# Receiver.net
KiCad netlist of a schematic drawn in Altium Designer
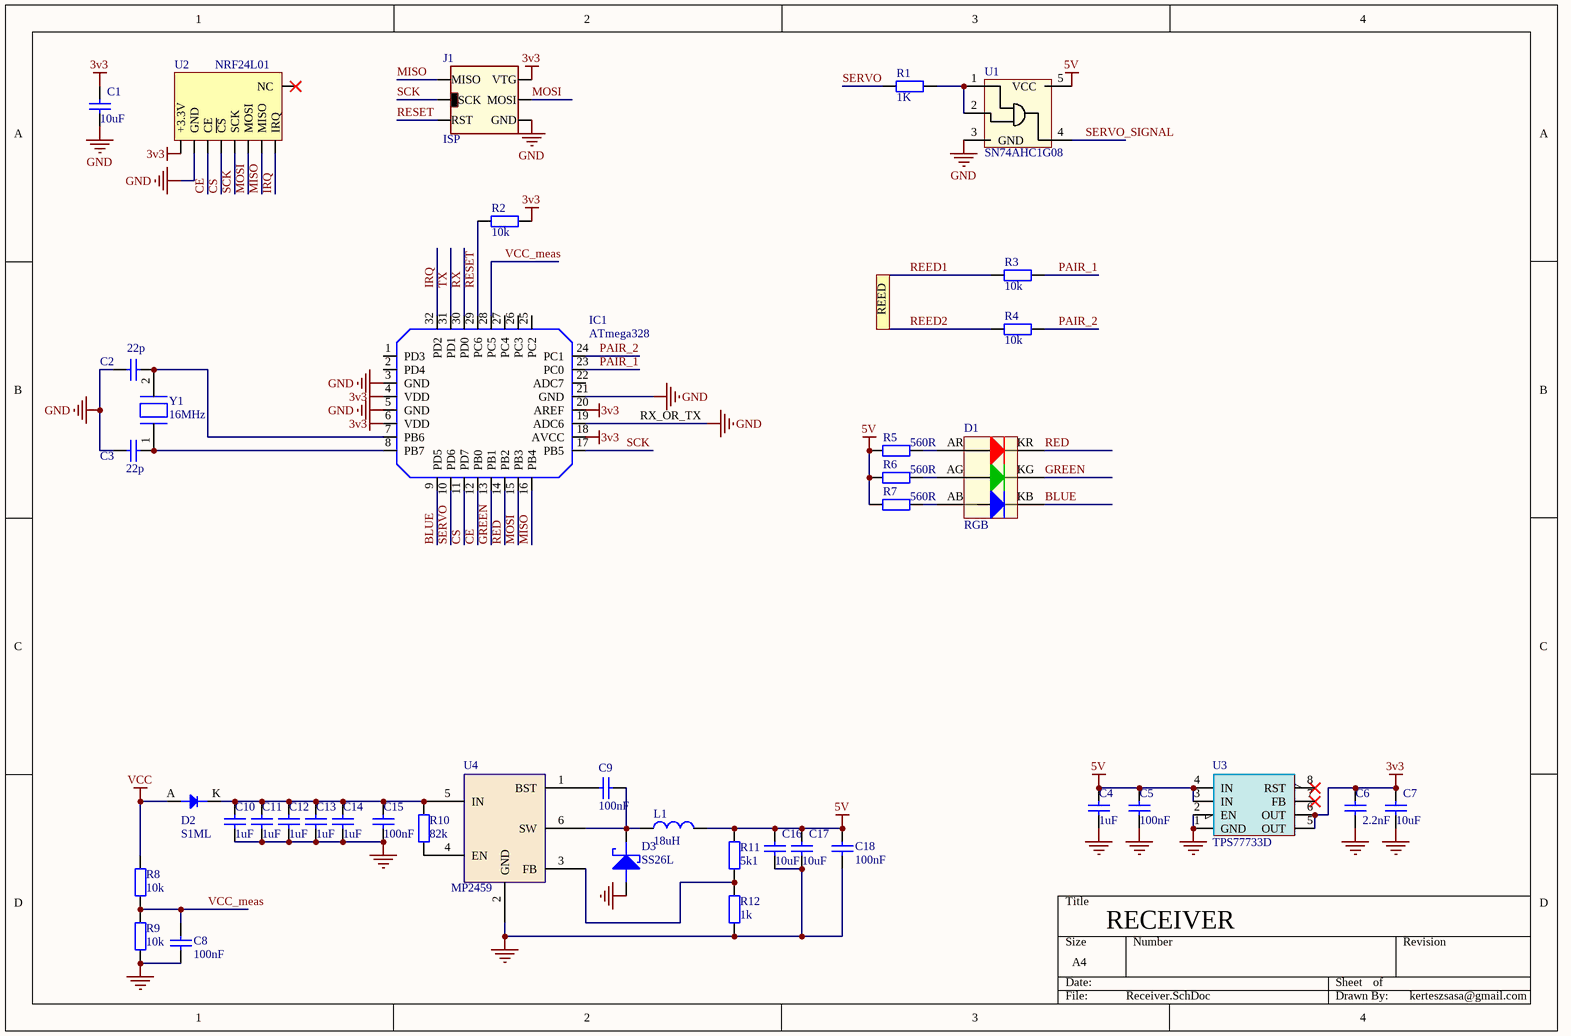
[diagram p0: Receiver.SchDoc]

(export (version "E")
  (design (tool "Eeschema 10.0.6"))
  (components
    (comp (ref "C1")
      (value "10uF")
      (footprint "FP_0603_CAP_080")
      (description "Capacitor")
      (libsource (lib "Miscellaneous Devices") (part "Cap"))
    )
    (comp (ref "C2")
      (value "22p")
      (footprint "FP_0603_CAP_080")
      (description "Capacitor")
      (libsource (lib "Miscellaneous Devices") (part "Cap"))
    )
    (comp (ref "C3")
      (value "22p")
      (footprint "FP_0603_CAP_080")
      (description "Capacitor")
      (libsource (lib "Miscellaneous Devices") (part "Cap"))
    )
    (comp (ref "C4")
      (value "1uF")
      (footprint "FP_0603_CAP_080")
      (description "Capacitor")
      (libsource (lib "Miscellaneous Devices") (part "Cap"))
    )
    (comp (ref "C5")
      (value "100nF")
      (footprint "FP_0603_CAP_080")
      (description "Capacitor")
      (libsource (lib "Miscellaneous Devices") (part "Cap"))
    )
    (comp (ref "C6")
      (value "2.2nF")
      (footprint "FP_0603_CAP_080")
      (description "Capacitor")
      (libsource (lib "Miscellaneous Devices") (part "Cap"))
    )
    (comp (ref "C7")
      (value "10uF")
      (footprint "FP_0603_CAP_080")
      (description "Capacitor")
      (libsource (lib "Miscellaneous Devices") (part "Cap"))
    )
    (comp (ref "C8")
      (value "100nF")
      (footprint "FP_0603_CAP_080")
      (description "Capacitor")
      (libsource (lib "Miscellaneous Devices") (part "Cap"))
    )
    (comp (ref "C9")
      (value "100nF")
      (footprint "FP_0603_CAP_080")
      (description "Capacitor")
      (libsource (lib "Miscellaneous Devices") (part "Cap"))
    )
    (comp (ref "C10")
      (value "1uF")
      (footprint "FP_0805_CAP_145")
      (description "Capacitor")
      (libsource (lib "Capacitor") (part "CAP"))
    )
    (comp (ref "C11")
      (value "1uF")
      (footprint "FP_0805_CAP_145")
      (description "Capacitor")
      (libsource (lib "Capacitor") (part "CAP"))
    )
    (comp (ref "C12")
      (value "1uF")
      (footprint "FP_0805_CAP_145")
      (description "Capacitor")
      (libsource (lib "Capacitor") (part "CAP"))
    )
    (comp (ref "C13")
      (value "1uF")
      (footprint "FP_0805_CAP_145")
      (description "Capacitor")
      (libsource (lib "Capacitor") (part "CAP"))
    )
    (comp (ref "C14")
      (value "1uF")
      (footprint "FP_0805_CAP_145")
      (description "Capacitor")
      (libsource (lib "Capacitor") (part "CAP"))
    )
    (comp (ref "C15")
      (value "100nF")
      (footprint "FP_0603_CAP_080")
      (description "Capacitor")
      (libsource (lib "Miscellaneous Devices") (part "Cap"))
    )
    (comp (ref "C16")
      (value "10uF")
      (footprint "FP_0603_CAP_080")
      (description "Capacitor")
      (libsource (lib "Miscellaneous Devices") (part "Cap"))
    )
    (comp (ref "C17")
      (value "10uF")
      (footprint "FP_0603_CAP_080")
      (description "Capacitor")
      (libsource (lib "Miscellaneous Devices") (part "Cap"))
    )
    (comp (ref "C18")
      (value "100nF")
      (footprint "FP_0603_CAP_080")
      (description "Capacitor")
      (libsource (lib "Miscellaneous Devices") (part "Cap"))
    )
    (comp (ref "D1")
      (value "RGB")
      (footprint "RGB_LED_5.0x5.0mm")
      (description "LED_RGB_6_PIN")
      (libsource (lib "Led_optical") (part "LED_RGB_6_PIN"))
    )
    (comp (ref "D2")
      (value "S1ML")
      (footprint "subsma")
      (description "Diode")
      (libsource (lib "Diode") (part "DIODE"))
    )
    (comp (ref "D3")
      (value "SS26L")
      (footprint "subsma")
      (description "NXP - PMEG3020EJ,115 - SCHOTTKY RECT 30V 2A SOD323F")
      (libsource (lib "Diode") (part "SCHOTTKY"))
    )
    (comp (ref "IC1") (value "ATmega328") (footprint "TQFP32_N") (libsource (lib "uC") (part "ATmega328")))
    (comp (ref "J1")
      (value "ISP")
      (footprint "AVR_ISP")
      (description "Programozó csatlakozó")
      (libsource (lib "Connector") (part "ISP"))
    )
    (comp (ref "L1")
      (value "18uH")
      (footprint "SDR0403_IND_4.5x5mm")
      (description "Inductor")
      (libsource (lib "Inductor") (part "L"))
    )
    (comp (ref "R1")
      (value "1K")
      (footprint "FP_0603_RES")
      (description "Resistor")
      (libsource (lib "") (part "RES_1"))
    )
    (comp (ref "R2")
      (value "10k")
      (footprint "FP_0603_RES")
      (description "Resistor")
      (libsource (lib "Miscellaneous Devices") (part "Res3"))
    )
    (comp (ref "R3")
      (value "10k")
      (footprint "FP_0603_RES")
      (description "Resistor")
      (libsource (lib "Miscellaneous Devices") (part "Res3"))
    )
    (comp (ref "R4")
      (value "10k")
      (footprint "FP_0603_RES")
      (description "Resistor")
      (libsource (lib "Miscellaneous Devices") (part "Res3"))
    )
    (comp (ref "R5")
      (value "560R")
      (footprint "FP_0603_RES")
      (description "Resistor")
      (libsource (lib "") (part "Res3_1"))
    )
    (comp (ref "R6")
      (value "560R")
      (footprint "FP_0603_RES")
      (description "Resistor")
      (libsource (lib "") (part "Res3_1"))
    )
    (comp (ref "R7")
      (value "560R")
      (footprint "FP_0603_RES")
      (description "Resistor")
      (libsource (lib "") (part "Res3_1"))
    )
    (comp (ref "R8")
      (value "10k")
      (footprint "FP_0603_RES")
      (description "Resistor")
      (libsource (lib "") (part "Res3_3"))
    )
    (comp (ref "R9")
      (value "10k")
      (footprint "FP_0603_RES")
      (description "Resistor")
      (libsource (lib "") (part "Res3_3"))
    )
    (comp (ref "R10")
      (value "82k")
      (footprint "FP_0603_RES")
      (description "Resistor")
      (libsource (lib "Resistor") (part "RES"))
    )
    (comp (ref "R11")
      (value "5k1")
      (footprint "FP_0603_RES")
      (description "Resistor")
      (libsource (lib "") (part "Res3_2"))
    )
    (comp (ref "R12")
      (value "1k")
      (footprint "FP_0603_RES")
      (description "Resistor")
      (libsource (lib "") (part "Res3_2"))
    )
    (comp (ref "U1")
      (value "SN74AHC1G08")
      (footprint "GATE_SOT23-5")
      (description "1x2-INPUT AND-GATE")
      (libsource (lib "Logic_gate") (part "SN74AHC1G08"))
    )
    (comp (ref "U2")
      (value "NRF24L01")
      (footprint "NRF24L01_SMD")
      (description "2.4Ghz RF module")
      (libsource (lib "Modul") (part "NRF24L01"))
    )
    (comp (ref "U3")
      (value "TPS77733D")
      (footprint "DIGITAL_SOIC8")
      (description "LDO Voltage Regulators Fast-Tran-Res 750-mA")
      (libsource (lib "TPS77733D") (part "TPS77733D"))
    )
    (comp (ref "U4")
      (value "MP2459")
      (footprint "Supply_SOT23-6")
      (description "0.5A, 55V, 480kHz  Step-Down Converter in a TSOT23-6")
      (libsource (lib "Supply") (part "MP2459"))
    )
    (comp (ref "Y1")
      (value "16MHz")
      (footprint "FP_CRYSTAL_HC49_SMD")
      (description "Standard HC49 quartz")
      (libsource (lib "Fufi_altium_lib") (part "XTAL HC49"))
    )
  )
  (nets
    (net (code "1") (name "/BLUE") (class "Default")
      (node (ref "D1") (pin "KB") (pinfunction "R_KB") (pintype "passive"))
      (node (ref "IC1") (pin "9") (pinfunction "PD5_9") (pintype "passive"))
    )
    (net (code "2") (name "/CE") (class "Default")
      (node (ref "IC1") (pin "12") (pinfunction "PB0_12") (pintype "passive"))
      (node (ref "U2") (pin "3") (pinfunction "CE_3") (pintype "passive"))
    )
    (net (code "3") (name "/CS") (class "Default")
      (node (ref "IC1") (pin "11") (pinfunction "PD7_11") (pintype "passive"))
      (node (ref "U2") (pin "4") (pinfunction "~{CS}_4") (pintype "passive"))
    )
    (net (code "4") (name "/GREEN") (class "Default")
      (node (ref "D1") (pin "KG") (pinfunction "G_KG") (pintype "passive"))
      (node (ref "IC1") (pin "13") (pinfunction "PB1_13") (pintype "passive"))
    )
    (net (code "5") (name "/IRQ") (class "Default")
      (node (ref "IC1") (pin "32") (pinfunction "PD2_32") (pintype "passive"))
      (node (ref "U2") (pin "8") (pinfunction "IRQ_8") (pintype "passive"))
    )
    (net (code "6") (name "/MISO") (class "Default")
      (node (ref "IC1") (pin "16") (pinfunction "PB4_16") (pintype "passive"))
      (node (ref "J1") (pin "1") (pinfunction "MISO_1") (pintype "passive"))
      (node (ref "U2") (pin "7") (pinfunction "MISO_7") (pintype "passive"))
    )
    (net (code "7") (name "/MOSI") (class "Default")
      (node (ref "IC1") (pin "15") (pinfunction "PB3_15") (pintype "passive"))
      (node (ref "J1") (pin "4") (pinfunction "MOSI_4") (pintype "passive"))
      (node (ref "U2") (pin "6") (pinfunction "MOSI_6") (pintype "passive"))
    )
    (net (code "8") (name "/PAIR_1") (class "Default")
      (node (ref "IC1") (pin "23") (pinfunction "PC0_23") (pintype "passive"))
      (node (ref "R3") (pin "2") (pinfunction "2_2") (pintype "passive"))
    )
    (net (code "9") (name "/PAIR_2") (class "Default")
      (node (ref "IC1") (pin "24") (pinfunction "PC1_24") (pintype "passive"))
      (node (ref "R4") (pin "2") (pinfunction "2_2") (pintype "passive"))
    )
    (net (code "10") (name "/RED") (class "Default")
      (node (ref "D1") (pin "KR") (pinfunction "B_KR") (pintype "passive"))
      (node (ref "IC1") (pin "14") (pinfunction "PB2_14") (pintype "passive"))
    )
    (net (code "11") (name "/REED1") (class "Default")
      (node (ref "R3") (pin "1") (pinfunction "1_1") (pintype "passive"))
    )
    (net (code "12") (name "/REED2") (class "Default")
      (node (ref "R4") (pin "1") (pinfunction "1_1") (pintype "passive"))
    )
    (net (code "13") (name "/RESET") (class "Default")
      (node (ref "IC1") (pin "29") (pinfunction "PC6_29") (pintype "passive"))
      (node (ref "J1") (pin "5") (pinfunction "RST_5") (pintype "passive"))
      (node (ref "R2") (pin "1") (pinfunction "1_1") (pintype "passive"))
    )
    (net (code "14") (name "/RX") (class "Default")
      (node (ref "IC1") (pin "30") (pinfunction "PD0_30") (pintype "passive"))
    )
    (net (code "15") (name "/SCK") (class "Default")
      (node (ref "IC1") (pin "17") (pinfunction "PB5_17") (pintype "passive"))
      (node (ref "J1") (pin "3") (pinfunction "SCK_3") (pintype "passive"))
      (node (ref "U2") (pin "5") (pinfunction "SCK_5") (pintype "passive"))
    )
    (net (code "16") (name "/SERVO") (class "Default")
      (node (ref "IC1") (pin "10") (pinfunction "PD6_10") (pintype "passive"))
      (node (ref "R1") (pin "1") (pinfunction "1_1") (pintype "passive"))
    )
    (net (code "17") (name "/SERVO_SIGNAL") (class "Default")
      (node (ref "U1") (pin "4") (pinfunction "Y_4") (pintype "passive"))
    )
    (net (code "18") (name "/TX") (class "Default")
      (node (ref "IC1") (pin "31") (pinfunction "PD1_31") (pintype "passive"))
    )
    (net (code "19") (name "/VCC_meas") (class "Default")
      (node (ref "C8") (pin "1") (pinfunction "1_1") (pintype "passive"))
      (node (ref "IC1") (pin "28") (pinfunction "PC5_28") (pintype "passive"))
      (node (ref "R8") (pin "1") (pinfunction "1_1") (pintype "passive"))
      (node (ref "R9") (pin "2") (pinfunction "2_2") (pintype "passive"))
    )
    (net (code "20") (name "3v3") (class "Default")
      (node (ref "C1") (pin "2") (pinfunction "2_2") (pintype "passive"))
      (node (ref "C6") (pin "2") (pinfunction "2_2") (pintype "passive"))
      (node (ref "C7") (pin "2") (pinfunction "2_2") (pintype "passive"))
      (node (ref "IC1") (pin "18") (pinfunction "AVCC_18") (pintype "passive"))
      (node (ref "IC1") (pin "20") (pinfunction "AREF_20") (pintype "passive"))
      (node (ref "IC1") (pin "4") (pinfunction "VDD_4") (pintype "passive"))
      (node (ref "IC1") (pin "6") (pinfunction "VDD_6") (pintype "passive"))
      (node (ref "J1") (pin "2") (pinfunction "VTG_2") (pintype "passive"))
      (node (ref "R2") (pin "2") (pinfunction "2_2") (pintype "passive"))
      (node (ref "U2") (pin "1") (pinfunction "+3.3V_1") (pintype "passive"))
      (node (ref "U3") (pin "5") (pinfunction "OUT_5") (pintype "passive"))
      (node (ref "U3") (pin "6") (pinfunction "OUT_6") (pintype "passive"))
    )
    (net (code "21") (name "5V") (class "Default")
      (node (ref "C16") (pin "2") (pinfunction "2_2") (pintype "passive"))
      (node (ref "C17") (pin "2") (pinfunction "2_2") (pintype "passive"))
      (node (ref "C18") (pin "1") (pinfunction "1_1") (pintype "passive"))
      (node (ref "C4") (pin "2") (pinfunction "2_2") (pintype "passive"))
      (node (ref "C5") (pin "2") (pinfunction "2_2") (pintype "passive"))
      (node (ref "L1") (pin "2") (pinfunction "2_2") (pintype "passive"))
      (node (ref "R11") (pin "1") (pinfunction "1_1") (pintype "passive"))
      (node (ref "R5") (pin "2") (pinfunction "2_2") (pintype "passive"))
      (node (ref "R6") (pin "2") (pinfunction "2_2") (pintype "passive"))
      (node (ref "R7") (pin "2") (pinfunction "2_2") (pintype "passive"))
      (node (ref "U1") (pin "5") (pinfunction "VCC_5") (pintype "passive"))
      (node (ref "U3") (pin "3") (pinfunction "IN_3") (pintype "passive"))
      (node (ref "U3") (pin "4") (pinfunction "IN_4") (pintype "passive"))
    )
    (net (code "22") (name "GND") (class "Default")
      (node (ref "C1") (pin "1") (pinfunction "1_1") (pintype "passive"))
      (node (ref "C10") (pin "1") (pinfunction "1_1") (pintype "passive"))
      (node (ref "C11") (pin "1") (pinfunction "1_1") (pintype "passive"))
      (node (ref "C12") (pin "1") (pinfunction "1_1") (pintype "passive"))
      (node (ref "C13") (pin "1") (pinfunction "1_1") (pintype "passive"))
      (node (ref "C14") (pin "1") (pinfunction "1_1") (pintype "passive"))
      (node (ref "C15") (pin "2") (pinfunction "2_2") (pintype "passive"))
      (node (ref "C16") (pin "1") (pinfunction "1_1") (pintype "passive"))
      (node (ref "C17") (pin "1") (pinfunction "1_1") (pintype "passive"))
      (node (ref "C18") (pin "2") (pinfunction "2_2") (pintype "passive"))
      (node (ref "C2") (pin "1") (pinfunction "1_1") (pintype "passive"))
      (node (ref "C3") (pin "1") (pinfunction "1_1") (pintype "passive"))
      (node (ref "C4") (pin "1") (pinfunction "1_1") (pintype "passive"))
      (node (ref "C5") (pin "1") (pinfunction "1_1") (pintype "passive"))
      (node (ref "C6") (pin "1") (pinfunction "1_1") (pintype "passive"))
      (node (ref "C7") (pin "1") (pinfunction "1_1") (pintype "passive"))
      (node (ref "C8") (pin "2") (pinfunction "2_2") (pintype "passive"))
      (node (ref "D3") (pin "A") (pinfunction "A_A") (pintype "passive"))
      (node (ref "IC1") (pin "19") (pinfunction "ADC6_19") (pintype "passive"))
      (node (ref "IC1") (pin "21") (pinfunction "GND_21") (pintype "passive"))
      (node (ref "IC1") (pin "3") (pinfunction "GND_3") (pintype "passive"))
      (node (ref "IC1") (pin "5") (pinfunction "GND_5") (pintype "passive"))
      (node (ref "J1") (pin "6") (pinfunction "GND_6") (pintype "passive"))
      (node (ref "R12") (pin "2") (pinfunction "2_2") (pintype "passive"))
      (node (ref "R9") (pin "1") (pinfunction "1_1") (pintype "passive"))
      (node (ref "U1") (pin "3") (pinfunction "GND_3") (pintype "passive"))
      (node (ref "U2") (pin "2") (pinfunction "GND_2") (pintype "passive"))
      (node (ref "U3") (pin "1") (pinfunction "GND_1") (pintype "passive"))
      (node (ref "U3") (pin "2") (pinfunction "EN_2") (pintype "passive"))
      (node (ref "U4") (pin "2") (pinfunction "GND_2") (pintype "passive"))
    )
    (net (code "23") (name "Net-(D1-A-PadAB)") (class "Default")
      (node (ref "D1") (pin "AB") (pinfunction "A_AB") (pintype "passive"))
      (node (ref "R7") (pin "1") (pinfunction "1_1") (pintype "passive"))
    )
    (net (code "24") (name "Net-(D1-A-PadAG)") (class "Default")
      (node (ref "D1") (pin "AG") (pinfunction "A_AG") (pintype "passive"))
      (node (ref "R6") (pin "1") (pinfunction "1_1") (pintype "passive"))
    )
    (net (code "25") (name "Net-(D1-A-PadAR)") (class "Default")
      (node (ref "D1") (pin "AR") (pinfunction "A_AR") (pintype "passive"))
      (node (ref "R5") (pin "1") (pinfunction "1_1") (pintype "passive"))
    )
    (net (code "26") (name "Net-(IC1-PB6)") (class "Default")
      (node (ref "C2") (pin "2") (pinfunction "2_2") (pintype "passive"))
      (node (ref "IC1") (pin "7") (pinfunction "PB6_7") (pintype "passive"))
      (node (ref "Y1") (pin "2") (pinfunction "2_2") (pintype "passive"))
    )
    (net (code "27") (name "Net-(IC1-PB7)") (class "Default")
      (node (ref "C3") (pin "2") (pinfunction "2_2") (pintype "passive"))
      (node (ref "IC1") (pin "8") (pinfunction "PB7_8") (pintype "passive"))
      (node (ref "Y1") (pin "1") (pinfunction "1_1") (pintype "passive"))
    )
    (net (code "28") (name "Net-(U1-A)") (class "Default")
      (node (ref "R1") (pin "2") (pinfunction "2_2") (pintype "passive"))
      (node (ref "U1") (pin "1") (pinfunction "A_1") (pintype "passive"))
      (node (ref "U1") (pin "2") (pinfunction "B_2") (pintype "passive"))
    )
    (net (code "29") (name "Net-(U4-BST)") (class "Default")
      (node (ref "C9") (pin "2") (pinfunction "2_2") (pintype "passive"))
      (node (ref "U4") (pin "1") (pinfunction "BST_1") (pintype "passive"))
    )
    (net (code "30") (name "Net-(U4-EN)") (class "Default")
      (node (ref "R10") (pin "2") (pinfunction "2_2") (pintype "passive"))
      (node (ref "U4") (pin "4") (pinfunction "EN_4") (pintype "passive"))
    )
    (net (code "31") (name "Net-(U4-FB)") (class "Default")
      (node (ref "R11") (pin "2") (pinfunction "2_2") (pintype "passive"))
      (node (ref "R12") (pin "1") (pinfunction "1_1") (pintype "passive"))
      (node (ref "U4") (pin "3") (pinfunction "FB_3") (pintype "passive"))
    )
    (net (code "32") (name "Net-(U4-IN)") (class "Default")
      (node (ref "C10") (pin "2") (pinfunction "2_2") (pintype "passive"))
      (node (ref "C11") (pin "2") (pinfunction "2_2") (pintype "passive"))
      (node (ref "C12") (pin "2") (pinfunction "2_2") (pintype "passive"))
      (node (ref "C13") (pin "2") (pinfunction "2_2") (pintype "passive"))
      (node (ref "C14") (pin "2") (pinfunction "2_2") (pintype "passive"))
      (node (ref "C15") (pin "1") (pinfunction "1_1") (pintype "passive"))
      (node (ref "D2") (pin "K") (pinfunction "K_K") (pintype "passive"))
      (node (ref "R10") (pin "1") (pinfunction "1_1") (pintype "passive"))
      (node (ref "U4") (pin "5") (pinfunction "IN_5") (pintype "passive"))
    )
    (net (code "33") (name "Net-(U4-SW)") (class "Default")
      (node (ref "C9") (pin "1") (pinfunction "1_1") (pintype "passive"))
      (node (ref "D3") (pin "K") (pinfunction "K_K") (pintype "passive"))
      (node (ref "L1") (pin "1") (pinfunction "1_1") (pintype "passive"))
      (node (ref "U4") (pin "6") (pinfunction "SW_6") (pintype "passive"))
    )
    (net (code "34") (name "VCC") (class "Default")
      (node (ref "D2") (pin "A") (pinfunction "A_A") (pintype "passive"))
      (node (ref "R8") (pin "2") (pinfunction "2_2") (pintype "passive"))
    )
    (net (code "35") (name "unconnected-(IC1-ADC7-Pad22)") (class "Default")
      (node (ref "IC1") (pin "22") (pinfunction "ADC7_22") (pintype "passive"))
    )
    (net (code "36") (name "unconnected-(IC1-PC2-Pad25)") (class "Default")
      (node (ref "IC1") (pin "25") (pinfunction "PC2_25") (pintype "passive"))
    )
    (net (code "37") (name "unconnected-(IC1-PC3-Pad26)") (class "Default")
      (node (ref "IC1") (pin "26") (pinfunction "PC3_26") (pintype "passive"))
    )
    (net (code "38") (name "unconnected-(IC1-PC4-Pad27)") (class "Default")
      (node (ref "IC1") (pin "27") (pinfunction "PC4_27") (pintype "passive"))
    )
    (net (code "39") (name "unconnected-(IC1-PD3-Pad1)") (class "Default")
      (node (ref "IC1") (pin "1") (pinfunction "PD3_1") (pintype "passive"))
    )
    (net (code "40") (name "unconnected-(IC1-PD4-Pad2)") (class "Default")
      (node (ref "IC1") (pin "2") (pinfunction "PD4_2") (pintype "passive"))
    )
    (net (code "41") (name "unconnected-(U2-NC-Pad9)") (class "Default")
      (node (ref "U2") (pin "9") (pinfunction "NC_9") (pintype "passive+no_connect"))
    )
    (net (code "42") (name "unconnected-(U3-FB-Pad7)") (class "Default")
      (node (ref "U3") (pin "7") (pinfunction "FB_7") (pintype "passive+no_connect"))
    )
    (net (code "43") (name "unconnected-(U3-RST-Pad8)") (class "Default")
      (node (ref "U3") (pin "8") (pinfunction "RST_8") (pintype "passive+no_connect"))
    )
  )
)
